# glowstick_schematic.net
KiCad netlist of a schematic drawn in EasyEDA
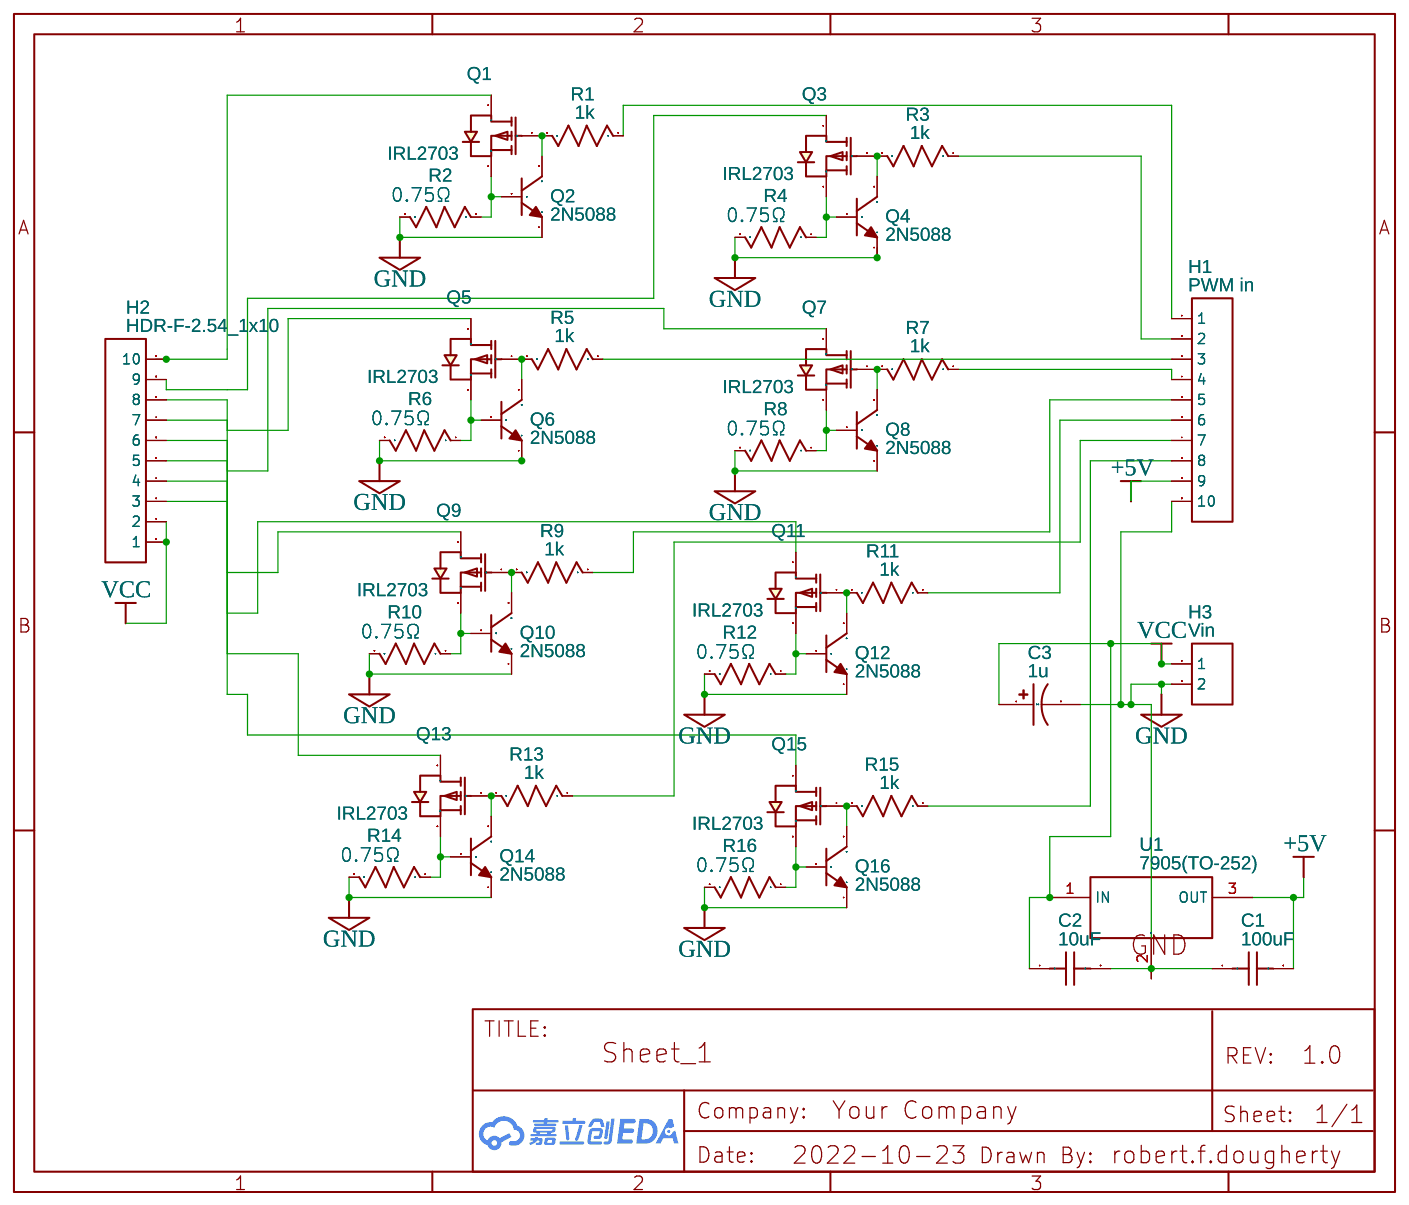
[diagram p0: schematic sheet]

(export (version "E")
  (design (tool "Eeschema 10.0.6"))
  (components
    (comp (ref "C1") (value "100uF") (libsource (lib "") (part "C_0603_US")))
    (comp (ref "C2") (value "10uF") (libsource (lib "") (part "C_0603_US")))
    (comp (ref "C3") (value "1u") (libsource (lib "") (part "CE_TH_D10.0×F5.0_US")))
    (comp (ref "H1") (value "PWM in") (libsource (lib "") (part "HDR-F-2.54_1x10_1")))
    (comp (ref "H2") (value "HDR-F-2.54_1x10") (libsource (lib "") (part "HDR-F-2.54_1x10")))
    (comp (ref "H3") (value "Vin") (libsource (lib "") (part "HDR-F-2.54_1x2")))
    (comp (ref "Q1")
      (value "IRL2703")
      (fields (field (name "Manufacturer Part") "IRF5210STRLPBF") (field (name "Manufacturer") "IR"))
      (libsource (lib "") (part "IRF5210"))
    )
    (comp (ref "Q2")
      (value "2N5088")
      (fields (field (name "Manufacturer Part") "2N3904") (field (name "Manufacturer") "SEMTECH"))
      (libsource (lib "") (part "2N3904(TO-92)"))
    )
    (comp (ref "Q3")
      (value "IRL2703")
      (fields (field (name "Manufacturer Part") "IRF5210STRLPBF") (field (name "Manufacturer") "IR"))
      (libsource (lib "") (part "IRF5210"))
    )
    (comp (ref "Q4")
      (value "2N5088")
      (fields (field (name "Manufacturer Part") "2N3904") (field (name "Manufacturer") "SEMTECH"))
      (libsource (lib "") (part "2N3904(TO-92)"))
    )
    (comp (ref "Q5")
      (value "IRL2703")
      (fields (field (name "Manufacturer Part") "IRF5210STRLPBF") (field (name "Manufacturer") "IR"))
      (libsource (lib "") (part "IRF5210"))
    )
    (comp (ref "Q6")
      (value "2N5088")
      (fields (field (name "Manufacturer Part") "2N3904") (field (name "Manufacturer") "SEMTECH"))
      (libsource (lib "") (part "2N3904(TO-92)"))
    )
    (comp (ref "Q7")
      (value "IRL2703")
      (fields (field (name "Manufacturer Part") "IRF5210STRLPBF") (field (name "Manufacturer") "IR"))
      (libsource (lib "") (part "IRF5210"))
    )
    (comp (ref "Q8")
      (value "2N5088")
      (fields (field (name "Manufacturer Part") "2N3904") (field (name "Manufacturer") "SEMTECH"))
      (libsource (lib "") (part "2N3904(TO-92)"))
    )
    (comp (ref "Q9")
      (value "IRL2703")
      (fields (field (name "Manufacturer Part") "IRF5210STRLPBF") (field (name "Manufacturer") "IR"))
      (libsource (lib "") (part "IRF5210"))
    )
    (comp (ref "Q10")
      (value "2N5088")
      (fields (field (name "Manufacturer Part") "2N3904") (field (name "Manufacturer") "SEMTECH"))
      (libsource (lib "") (part "2N3904(TO-92)"))
    )
    (comp (ref "Q11")
      (value "IRL2703")
      (fields (field (name "Manufacturer Part") "IRF5210STRLPBF") (field (name "Manufacturer") "IR"))
      (libsource (lib "") (part "IRF5210"))
    )
    (comp (ref "Q12")
      (value "2N5088")
      (fields (field (name "Manufacturer Part") "2N3904") (field (name "Manufacturer") "SEMTECH"))
      (libsource (lib "") (part "2N3904(TO-92)"))
    )
    (comp (ref "Q13")
      (value "IRL2703")
      (fields (field (name "Manufacturer Part") "IRF5210STRLPBF") (field (name "Manufacturer") "IR"))
      (libsource (lib "") (part "IRF5210"))
    )
    (comp (ref "Q14")
      (value "2N5088")
      (fields (field (name "Manufacturer Part") "2N3904") (field (name "Manufacturer") "SEMTECH"))
      (libsource (lib "") (part "2N3904(TO-92)"))
    )
    (comp (ref "Q15")
      (value "IRL2703")
      (fields (field (name "Manufacturer Part") "IRF5210STRLPBF") (field (name "Manufacturer") "IR"))
      (libsource (lib "") (part "IRF5210"))
    )
    (comp (ref "Q16")
      (value "2N5088")
      (fields (field (name "Manufacturer Part") "2N3904") (field (name "Manufacturer") "SEMTECH"))
      (libsource (lib "") (part "2N3904(TO-92)"))
    )
    (comp (ref "R1") (value "1k") (libsource (lib "") (part "R_0603_US")))
    (comp (ref "R2") (value "0.75Ω") (libsource (lib "") (part "R_0603_US")))
    (comp (ref "R3") (value "1k") (libsource (lib "") (part "R_0603_US")))
    (comp (ref "R4") (value "0.75Ω") (libsource (lib "") (part "R_0603_US")))
    (comp (ref "R5") (value "1k") (libsource (lib "") (part "R_0603_US")))
    (comp (ref "R6") (value "0.75Ω") (libsource (lib "") (part "R_0603_US")))
    (comp (ref "R7") (value "1k") (libsource (lib "") (part "R_0603_US")))
    (comp (ref "R8") (value "0.75Ω") (libsource (lib "") (part "R_0603_US")))
    (comp (ref "R9") (value "1k") (libsource (lib "") (part "R_0603_US")))
    (comp (ref "R10") (value "0.75Ω") (libsource (lib "") (part "R_0603_US")))
    (comp (ref "R11") (value "1k") (libsource (lib "") (part "R_0603_US")))
    (comp (ref "R12") (value "0.75Ω") (libsource (lib "") (part "R_0603_US")))
    (comp (ref "R13") (value "1k") (libsource (lib "") (part "R_0603_US")))
    (comp (ref "R14") (value "0.75Ω") (libsource (lib "") (part "R_0603_US")))
    (comp (ref "R15") (value "1k") (libsource (lib "") (part "R_0603_US")))
    (comp (ref "R16") (value "0.75Ω") (libsource (lib "") (part "R_0603_US")))
    (comp (ref "U1")
      (value "7905(TO-252)")
      (fields (field (name "Manufacturer Part") "CJ7905") (field (name "Manufacturer") "CJ"))
      (libsource (lib "") (part "7905(TO-252)"))
    )
  )
  (nets
    (net (code "1") (name "+5V") (class "Default")
      (node (ref "C1") (pin "2") (pinfunction "2_2") (pintype "unspecified"))
      (node (ref "H1") (pin "9") (pinfunction "9_9") (pintype "unspecified"))
      (node (ref "U1") (pin "3") (pinfunction "OUT_3") (pintype "passive"))
    )
    (net (code "2") (name "GND") (class "Default")
      (node (ref "C1") (pin "1") (pinfunction "1_1") (pintype "unspecified"))
      (node (ref "C2") (pin "2") (pinfunction "2_2") (pintype "unspecified"))
      (node (ref "C3") (pin "2") (pinfunction "2_2") (pintype "unspecified"))
      (node (ref "H1") (pin "10") (pinfunction "10_10") (pintype "unspecified"))
      (node (ref "H3") (pin "2") (pinfunction "2_2") (pintype "input"))
      (node (ref "Q10") (pin "1") (pinfunction "E_1") (pintype "unspecified"))
      (node (ref "Q12") (pin "1") (pinfunction "E_1") (pintype "unspecified"))
      (node (ref "Q14") (pin "1") (pinfunction "E_1") (pintype "unspecified"))
      (node (ref "Q16") (pin "1") (pinfunction "E_1") (pintype "unspecified"))
      (node (ref "Q2") (pin "1") (pinfunction "E_1") (pintype "unspecified"))
      (node (ref "Q4") (pin "1") (pinfunction "E_1") (pintype "unspecified"))
      (node (ref "Q6") (pin "1") (pinfunction "E_1") (pintype "unspecified"))
      (node (ref "Q8") (pin "1") (pinfunction "E_1") (pintype "unspecified"))
      (node (ref "R10") (pin "2") (pinfunction "2_2") (pintype "unspecified"))
      (node (ref "R12") (pin "2") (pinfunction "2_2") (pintype "unspecified"))
      (node (ref "R14") (pin "2") (pinfunction "2_2") (pintype "unspecified"))
      (node (ref "R16") (pin "2") (pinfunction "2_2") (pintype "unspecified"))
      (node (ref "R2") (pin "2") (pinfunction "2_2") (pintype "unspecified"))
      (node (ref "R4") (pin "2") (pinfunction "2_2") (pintype "unspecified"))
      (node (ref "R6") (pin "2") (pinfunction "2_2") (pintype "unspecified"))
      (node (ref "R8") (pin "2") (pinfunction "2_2") (pintype "unspecified"))
      (node (ref "U1") (pin "2") (pinfunction "GND_2") (pintype "passive"))
    )
    (net (code "3") (name "Net-(H1-Pad1)") (class "Default")
      (node (ref "H1") (pin "1") (pinfunction "1_1") (pintype "unspecified"))
      (node (ref "R1") (pin "1") (pinfunction "1_1") (pintype "unspecified"))
    )
    (net (code "4") (name "Net-(H1-Pad2)") (class "Default")
      (node (ref "H1") (pin "2") (pinfunction "2_2") (pintype "unspecified"))
      (node (ref "R3") (pin "1") (pinfunction "1_1") (pintype "unspecified"))
    )
    (net (code "5") (name "Net-(H1-Pad3)") (class "Default")
      (node (ref "H1") (pin "3") (pinfunction "3_3") (pintype "unspecified"))
      (node (ref "R5") (pin "1") (pinfunction "1_1") (pintype "unspecified"))
    )
    (net (code "6") (name "Net-(H1-Pad4)") (class "Default")
      (node (ref "H1") (pin "4") (pinfunction "4_4") (pintype "unspecified"))
      (node (ref "R7") (pin "1") (pinfunction "1_1") (pintype "unspecified"))
    )
    (net (code "7") (name "Net-(H1-Pad5)") (class "Default")
      (node (ref "H1") (pin "5") (pinfunction "5_5") (pintype "unspecified"))
      (node (ref "R9") (pin "1") (pinfunction "1_1") (pintype "unspecified"))
    )
    (net (code "8") (name "Net-(H1-Pad6)") (class "Default")
      (node (ref "H1") (pin "6") (pinfunction "6_6") (pintype "unspecified"))
      (node (ref "R11") (pin "1") (pinfunction "1_1") (pintype "unspecified"))
    )
    (net (code "9") (name "Net-(H1-Pad7)") (class "Default")
      (node (ref "H1") (pin "7") (pinfunction "7_7") (pintype "unspecified"))
      (node (ref "R13") (pin "1") (pinfunction "1_1") (pintype "unspecified"))
    )
    (net (code "10") (name "Net-(H1-Pad8)") (class "Default")
      (node (ref "H1") (pin "8") (pinfunction "8_8") (pintype "unspecified"))
      (node (ref "R15") (pin "1") (pinfunction "1_1") (pintype "unspecified"))
    )
    (net (code "11") (name "Net-(Q1-D)") (class "Default")
      (node (ref "H2") (pin "10") (pinfunction "10_10") (pintype "unspecified"))
      (node (ref "Q1") (pin "2") (pinfunction "D_2") (pintype "unspecified"))
    )
    (net (code "12") (name "Net-(Q1-G)") (class "Default")
      (node (ref "Q1") (pin "1") (pinfunction "G_1") (pintype "unspecified"))
      (node (ref "Q2") (pin "3") (pinfunction "C_3") (pintype "unspecified"))
      (node (ref "R1") (pin "2") (pinfunction "2_2") (pintype "unspecified"))
    )
    (net (code "13") (name "Net-(Q1-S)") (class "Default")
      (node (ref "Q1") (pin "3") (pinfunction "S_3") (pintype "unspecified"))
      (node (ref "Q2") (pin "2") (pinfunction "B_2") (pintype "unspecified"))
      (node (ref "R2") (pin "1") (pinfunction "1_1") (pintype "unspecified"))
    )
    (net (code "14") (name "Net-(Q3-D)") (class "Default")
      (node (ref "H2") (pin "9") (pinfunction "9_9") (pintype "unspecified"))
      (node (ref "Q3") (pin "2") (pinfunction "D_2") (pintype "unspecified"))
    )
    (net (code "15") (name "Net-(Q3-G)") (class "Default")
      (node (ref "Q3") (pin "1") (pinfunction "G_1") (pintype "unspecified"))
      (node (ref "Q4") (pin "3") (pinfunction "C_3") (pintype "unspecified"))
      (node (ref "R3") (pin "2") (pinfunction "2_2") (pintype "unspecified"))
    )
    (net (code "16") (name "Net-(Q3-S)") (class "Default")
      (node (ref "Q3") (pin "3") (pinfunction "S_3") (pintype "unspecified"))
      (node (ref "Q4") (pin "2") (pinfunction "B_2") (pintype "unspecified"))
      (node (ref "R4") (pin "1") (pinfunction "1_1") (pintype "unspecified"))
    )
    (net (code "17") (name "Net-(Q5-D)") (class "Default")
      (node (ref "H2") (pin "8") (pinfunction "8_8") (pintype "unspecified"))
      (node (ref "Q5") (pin "2") (pinfunction "D_2") (pintype "unspecified"))
    )
    (net (code "18") (name "Net-(Q5-G)") (class "Default")
      (node (ref "Q5") (pin "1") (pinfunction "G_1") (pintype "unspecified"))
      (node (ref "Q6") (pin "3") (pinfunction "C_3") (pintype "unspecified"))
      (node (ref "R5") (pin "2") (pinfunction "2_2") (pintype "unspecified"))
    )
    (net (code "19") (name "Net-(Q5-S)") (class "Default")
      (node (ref "Q5") (pin "3") (pinfunction "S_3") (pintype "unspecified"))
      (node (ref "Q6") (pin "2") (pinfunction "B_2") (pintype "unspecified"))
      (node (ref "R6") (pin "1") (pinfunction "1_1") (pintype "unspecified"))
    )
    (net (code "20") (name "Net-(Q7-D)") (class "Default")
      (node (ref "H2") (pin "7") (pinfunction "7_7") (pintype "unspecified"))
      (node (ref "Q7") (pin "2") (pinfunction "D_2") (pintype "unspecified"))
    )
    (net (code "21") (name "Net-(Q7-G)") (class "Default")
      (node (ref "Q7") (pin "1") (pinfunction "G_1") (pintype "unspecified"))
      (node (ref "Q8") (pin "3") (pinfunction "C_3") (pintype "unspecified"))
      (node (ref "R7") (pin "2") (pinfunction "2_2") (pintype "unspecified"))
    )
    (net (code "22") (name "Net-(Q7-S)") (class "Default")
      (node (ref "Q7") (pin "3") (pinfunction "S_3") (pintype "unspecified"))
      (node (ref "Q8") (pin "2") (pinfunction "B_2") (pintype "unspecified"))
      (node (ref "R8") (pin "1") (pinfunction "1_1") (pintype "unspecified"))
    )
    (net (code "23") (name "Net-(Q9-D)") (class "Default")
      (node (ref "H2") (pin "6") (pinfunction "6_6") (pintype "unspecified"))
      (node (ref "Q9") (pin "2") (pinfunction "D_2") (pintype "unspecified"))
    )
    (net (code "24") (name "Net-(Q10-B)") (class "Default")
      (node (ref "Q10") (pin "2") (pinfunction "B_2") (pintype "unspecified"))
      (node (ref "Q9") (pin "3") (pinfunction "S_3") (pintype "unspecified"))
      (node (ref "R10") (pin "1") (pinfunction "1_1") (pintype "unspecified"))
    )
    (net (code "25") (name "Net-(Q10-C)") (class "Default")
      (node (ref "Q10") (pin "3") (pinfunction "C_3") (pintype "unspecified"))
      (node (ref "Q9") (pin "1") (pinfunction "G_1") (pintype "unspecified"))
      (node (ref "R9") (pin "2") (pinfunction "2_2") (pintype "unspecified"))
    )
    (net (code "26") (name "Net-(Q11-D)") (class "Default")
      (node (ref "H2") (pin "5") (pinfunction "5_5") (pintype "unspecified"))
      (node (ref "Q11") (pin "2") (pinfunction "D_2") (pintype "unspecified"))
    )
    (net (code "27") (name "Net-(Q11-G)") (class "Default")
      (node (ref "Q11") (pin "1") (pinfunction "G_1") (pintype "unspecified"))
      (node (ref "Q12") (pin "3") (pinfunction "C_3") (pintype "unspecified"))
      (node (ref "R11") (pin "2") (pinfunction "2_2") (pintype "unspecified"))
    )
    (net (code "28") (name "Net-(Q11-S)") (class "Default")
      (node (ref "Q11") (pin "3") (pinfunction "S_3") (pintype "unspecified"))
      (node (ref "Q12") (pin "2") (pinfunction "B_2") (pintype "unspecified"))
      (node (ref "R12") (pin "1") (pinfunction "1_1") (pintype "unspecified"))
    )
    (net (code "29") (name "Net-(Q13-D)") (class "Default")
      (node (ref "H2") (pin "4") (pinfunction "4_4") (pintype "unspecified"))
      (node (ref "Q13") (pin "2") (pinfunction "D_2") (pintype "unspecified"))
    )
    (net (code "30") (name "Net-(Q13-G)") (class "Default")
      (node (ref "Q13") (pin "1") (pinfunction "G_1") (pintype "unspecified"))
      (node (ref "Q14") (pin "3") (pinfunction "C_3") (pintype "unspecified"))
      (node (ref "R13") (pin "2") (pinfunction "2_2") (pintype "unspecified"))
    )
    (net (code "31") (name "Net-(Q13-S)") (class "Default")
      (node (ref "Q13") (pin "3") (pinfunction "S_3") (pintype "unspecified"))
      (node (ref "Q14") (pin "2") (pinfunction "B_2") (pintype "unspecified"))
      (node (ref "R14") (pin "1") (pinfunction "1_1") (pintype "unspecified"))
    )
    (net (code "32") (name "Net-(Q15-D)") (class "Default")
      (node (ref "H2") (pin "3") (pinfunction "3_3") (pintype "unspecified"))
      (node (ref "Q15") (pin "2") (pinfunction "D_2") (pintype "unspecified"))
    )
    (net (code "33") (name "Net-(Q15-G)") (class "Default")
      (node (ref "Q15") (pin "1") (pinfunction "G_1") (pintype "unspecified"))
      (node (ref "Q16") (pin "3") (pinfunction "C_3") (pintype "unspecified"))
      (node (ref "R15") (pin "2") (pinfunction "2_2") (pintype "unspecified"))
    )
    (net (code "34") (name "Net-(Q15-S)") (class "Default")
      (node (ref "Q15") (pin "3") (pinfunction "S_3") (pintype "unspecified"))
      (node (ref "Q16") (pin "2") (pinfunction "B_2") (pintype "unspecified"))
      (node (ref "R16") (pin "1") (pinfunction "1_1") (pintype "unspecified"))
    )
    (net (code "35") (name "VCC") (class "Default")
      (node (ref "C2") (pin "1") (pinfunction "1_1") (pintype "unspecified"))
      (node (ref "C3") (pin "1") (pinfunction "1_1") (pintype "unspecified"))
      (node (ref "H2") (pin "1") (pinfunction "1_1") (pintype "unspecified"))
      (node (ref "H2") (pin "2") (pinfunction "2_2") (pintype "unspecified"))
      (node (ref "H3") (pin "1") (pinfunction "1_1") (pintype "input"))
      (node (ref "U1") (pin "1") (pinfunction "IN_1") (pintype "passive"))
    )
  )
)
